# xbee_Featherwing.net
KiCad netlist of a schematic drawn in EAGLE
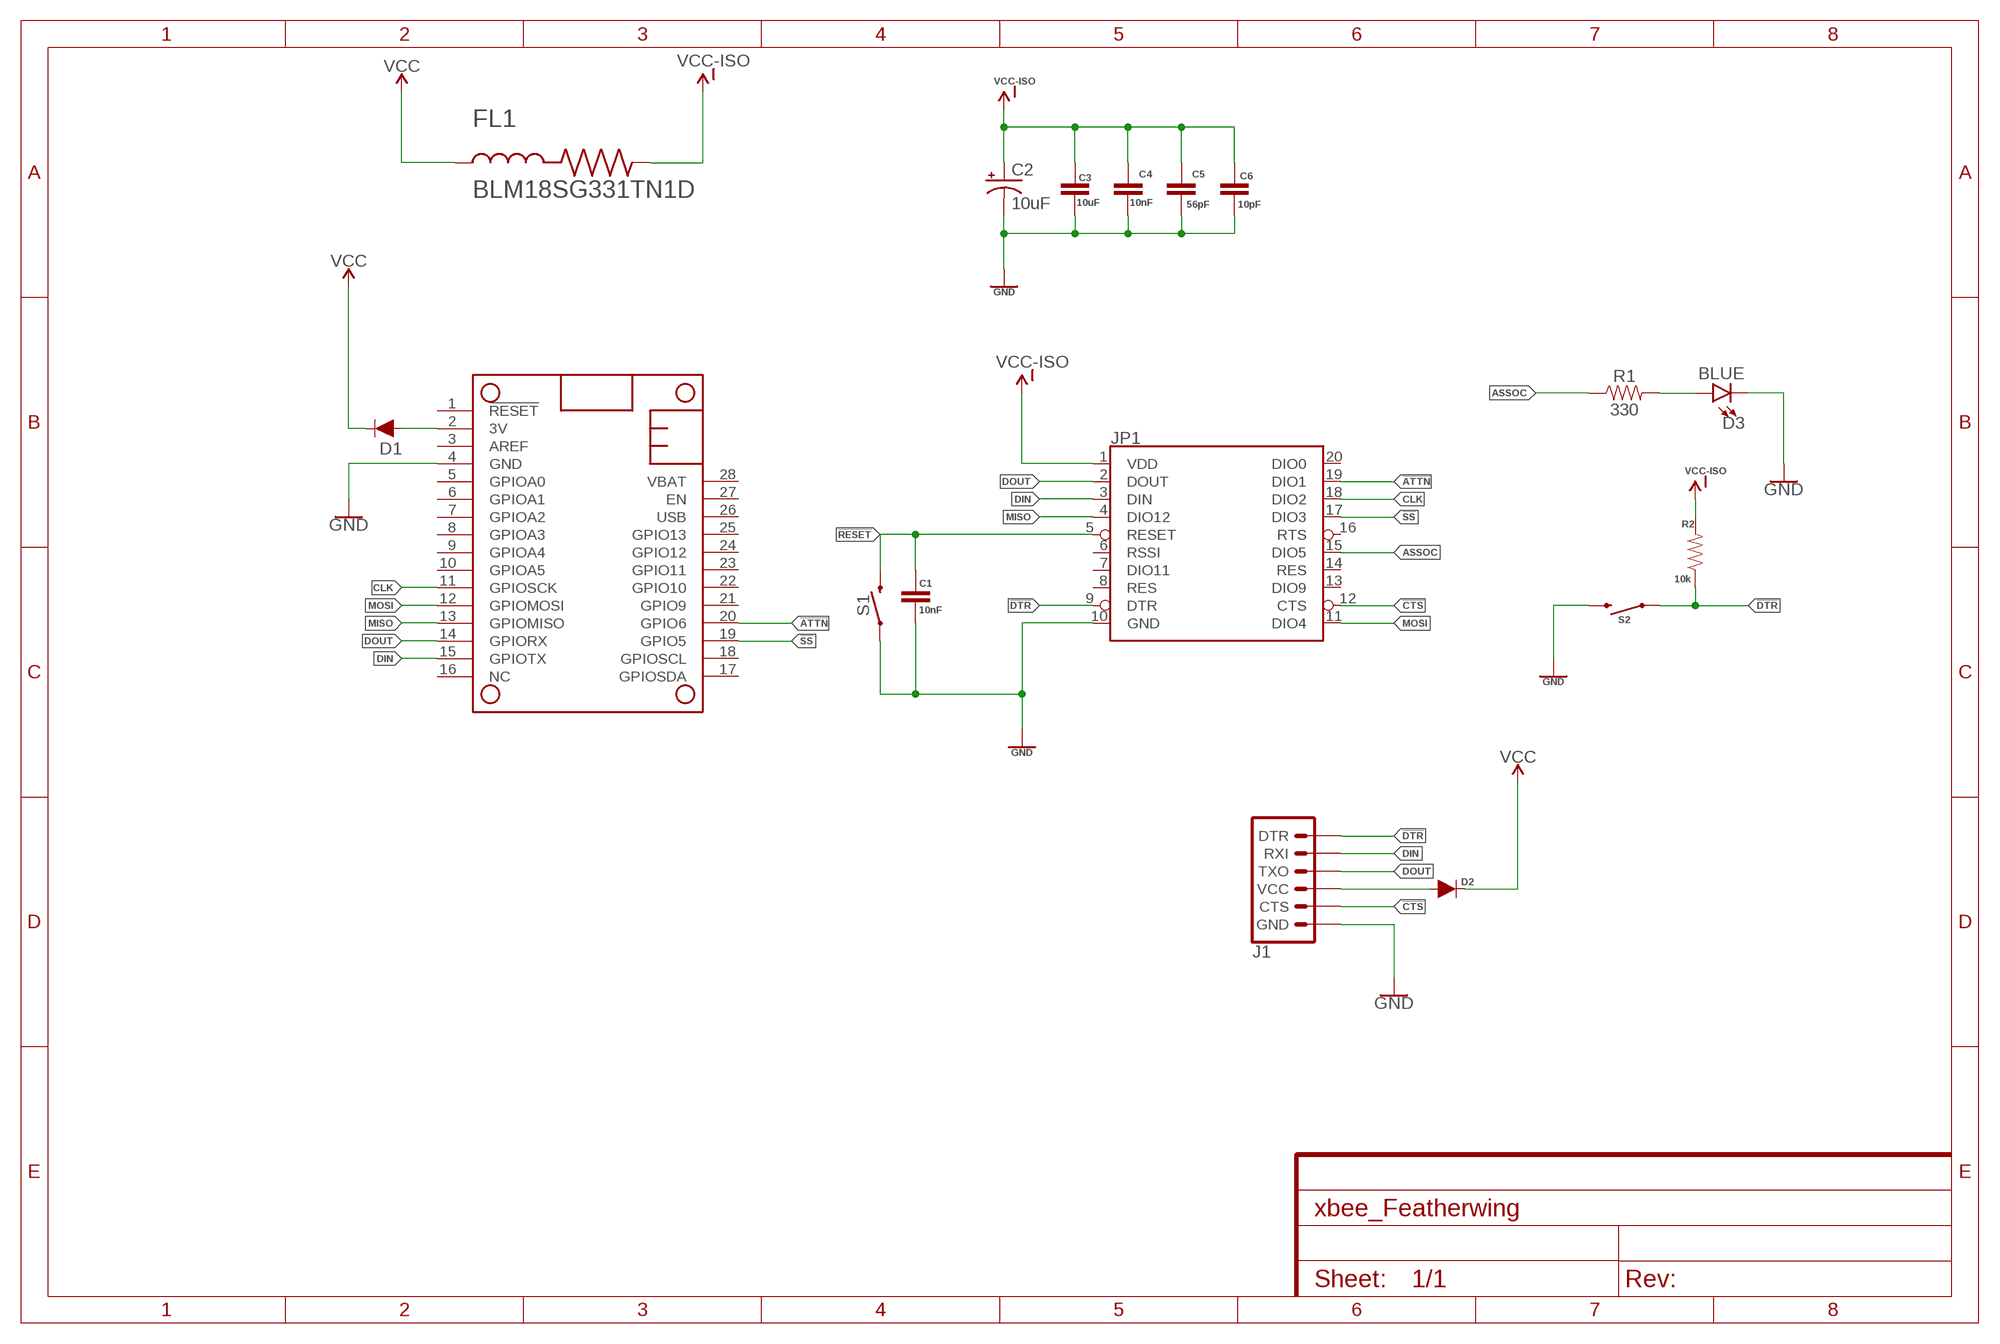
[diagram p0: schematic, sheet 1]

(export (version "E")
  (design (tool "Eeschema 10.0.6"))
  (components
    (comp (ref "C1")
      (value "10nF")
      (footprint "eagle-import:0603")
      (libsource (lib "eagle-import") (part "10NF-0603-50V-10%"))
    )
    (comp (ref "C2")
      (value "10uF")
      (footprint "eagle-import:EIA3216")
      (libsource (lib "eagle-import") (part "10UF-POLAR-EIA3216-16V-10%(TANT)"))
    )
    (comp (ref "C3")
      (value "10uF")
      (footprint "eagle-import:0603")
      (libsource (lib "eagle-import") (part "10UF-0603-6.3V-20%"))
    )
    (comp (ref "C4")
      (value "10nF")
      (footprint "eagle-import:0603")
      (libsource (lib "eagle-import") (part "10NF-0603-50V-10%"))
    )
    (comp (ref "C5")
      (value "56pF")
      (footprint "eagle-import:0603")
      (libsource (lib "eagle-import") (part "560PF-0603-50V-5%"))
    )
    (comp (ref "C6")
      (value "10pF")
      (footprint "eagle-import:0603")
      (libsource (lib "eagle-import") (part "10PF-0603-50V-5%"))
    )
    (comp (ref "D1")
      (value "250mA/100V")
      (footprint "eagle-import:SOD-323")
      (libsource (lib "eagle-import") (part "DIODE-BAS16J"))
    )
    (comp (ref "D2")
      (value "250mA/100V")
      (footprint "eagle-import:SOD-323")
      (libsource (lib "eagle-import") (part "DIODE-BAS16J"))
    )
    (comp (ref "D3")
      (value "BLUE")
      (footprint "eagle-import:LED-0603")
      (libsource (lib "eagle-import") (part "LED-BLUE0603"))
    )
    (comp (ref "FL1")
      (value "BLM18SG331TN1D")
      (footprint "eagle-import:BEADC1608X65N")
      (fields (field (name "MF") "Murata Electronics"))
      (libsource (lib "eagle-import") (part "BLM18SG331TN1D"))
    )
    (comp (ref "J1")
      (value "6_PIN_SERIAL_TARGETSILK")
      (footprint "eagle-import:6_PIN_SERIAL_TARGET_SIDE_W_SILK")
      (libsource (lib "eagle-import") (part "6_PIN_SERIAL_TARGETSILK"))
    )
    (comp (ref "JP1")
      (value "XBEESMD")
      (footprint "eagle-import:XBEE-SMD")
      (libsource (lib "eagle-import") (part "XBEESMD"))
    )
    (comp (ref "MS1")
      (value "FEATHERWINGXBEE")
      (footprint "eagle-import:FEATHERWING_XBEE")
      (libsource (lib "eagle-import") (part "FEATHERWINGXBEE"))
    )
    (comp (ref "R1")
      (value "330")
      (footprint "eagle-import:0603")
      (libsource (lib "eagle-import") (part "330OHM-0603-1/10W-1%"))
    )
    (comp (ref "R2")
      (value "10k")
      (footprint "eagle-import:0603")
      (libsource (lib "eagle-import") (part "10KOHM-0603-1/10W-1%"))
    )
    (comp (ref "S1")
      (value "MOMENTARY-SWITCH-SPST-PTH-6.0MM")
      (footprint "eagle-import:TACTILE_SWITCH_PTH_6.0MM")
      (libsource (lib "eagle-import") (part "MOMENTARY-SWITCH-SPST-PTH-6.0MM"))
    )
    (comp (ref "S2")
      (value "MOMENTARY-SWITCH-SPST-PTH-6.0MM")
      (footprint "eagle-import:TACTILE_SWITCH_PTH_6.0MM")
      (libsource (lib "eagle-import") (part "MOMENTARY-SWITCH-SPST-PTH-6.0MM"))
    )
  )
  (nets
    (net (code "1") (name "/USB") (class "Default")
      (node (ref "MS1") (pin "26") (pinfunction "USB_26") (pintype "power_in"))
    )
    (net (code "2") (name "/VBAT") (class "Default")
      (node (ref "MS1") (pin "28") (pinfunction "VBAT_28") (pintype "power_in"))
    )
    (net (code "3") (name "/~{ATTN}") (class "Default")
      (node (ref "JP1") (pin "19") (pinfunction "DIO1_19") (pintype "bidirectional"))
      (node (ref "MS1") (pin "20") (pinfunction "GPIO6_20") (pintype "bidirectional"))
    )
    (net (code "4") (name "/~{CTS}") (class "Default")
      (node (ref "J1") (pin "P$5") (pinfunction "CTS_P$5") (pintype "passive"))
      (node (ref "JP1") (pin "12") (pinfunction "CTS_12") (pintype "output"))
    )
    (net (code "5") (name "/~{DTR}") (class "Default")
      (node (ref "J1") (pin "P$1") (pinfunction "DTR_P$1") (pintype "passive"))
      (node (ref "JP1") (pin "9") (pinfunction "DTR_9") (pintype "bidirectional"))
      (node (ref "R2") (pin "1") (pinfunction "1_1") (pintype "passive"))
      (node (ref "S2") (pin "1") (pinfunction "1_1") (pintype "passive"))
    )
    (net (code "6") (name "/~{RESET}") (class "Default")
      (node (ref "C1") (pin "1") (pinfunction "1_1") (pintype "passive"))
      (node (ref "JP1") (pin "5") (pinfunction "RESET_5") (pintype "input"))
      (node (ref "S1") (pin "3") (pinfunction "2_3") (pintype "passive"))
    )
    (net (code "7") (name "/~{SS}") (class "Default")
      (node (ref "JP1") (pin "17") (pinfunction "DIO3_17") (pintype "bidirectional"))
      (node (ref "MS1") (pin "19") (pinfunction "GPIO5_19") (pintype "bidirectional"))
    )
    (net (code "8") (name "ASSOC") (class "Default")
      (node (ref "JP1") (pin "15") (pinfunction "DIO5_15") (pintype "bidirectional"))
      (node (ref "R1") (pin "1") (pinfunction "1_1") (pintype "passive"))
    )
    (net (code "9") (name "CLK") (class "Default")
      (node (ref "JP1") (pin "18") (pinfunction "DIO2_18") (pintype "bidirectional"))
      (node (ref "MS1") (pin "11") (pinfunction "GPIOSCK_11") (pintype "bidirectional"))
    )
    (net (code "10") (name "DIN") (class "Default")
      (node (ref "J1") (pin "P$3") (pinfunction "RXI_P$3") (pintype "passive"))
      (node (ref "JP1") (pin "3") (pinfunction "DIN_3") (pintype "input"))
      (node (ref "MS1") (pin "15") (pinfunction "GPIOTX_15") (pintype "bidirectional"))
    )
    (net (code "11") (name "DOUT") (class "Default")
      (node (ref "J1") (pin "P$2") (pinfunction "TXO_P$2") (pintype "passive"))
      (node (ref "JP1") (pin "2") (pinfunction "DOUT_2") (pintype "output"))
      (node (ref "MS1") (pin "14") (pinfunction "GPIORX_14") (pintype "bidirectional"))
    )
    (net (code "12") (name "GND") (class "Default")
      (node (ref "C1") (pin "2") (pinfunction "2_2") (pintype "passive"))
      (node (ref "C2") (pin "-") (pinfunction "-_-") (pintype "passive"))
      (node (ref "C3") (pin "2") (pinfunction "2_2") (pintype "passive"))
      (node (ref "C4") (pin "2") (pinfunction "2_2") (pintype "passive"))
      (node (ref "C5") (pin "2") (pinfunction "2_2") (pintype "passive"))
      (node (ref "C6") (pin "2") (pinfunction "2_2") (pintype "passive"))
      (node (ref "D3") (pin "C") (pinfunction "C_C") (pintype "passive"))
      (node (ref "J1") (pin "P$6") (pinfunction "GND_P$6") (pintype "passive"))
      (node (ref "JP1") (pin "10") (pinfunction "GND_10") (pintype "power_in"))
      (node (ref "MS1") (pin "4") (pinfunction "GND_4") (pintype "power_in"))
      (node (ref "S1") (pin "1") (pinfunction "1_1") (pintype "passive"))
      (node (ref "S2") (pin "3") (pinfunction "2_3") (pintype "passive"))
    )
    (net (code "13") (name "MISO") (class "Default")
      (node (ref "JP1") (pin "4") (pinfunction "DIO12_4") (pintype "bidirectional"))
      (node (ref "MS1") (pin "13") (pinfunction "GPIOMISO_13") (pintype "bidirectional"))
    )
    (net (code "14") (name "MOSI") (class "Default")
      (node (ref "JP1") (pin "11") (pinfunction "DIO4_11") (pintype "bidirectional"))
      (node (ref "MS1") (pin "12") (pinfunction "GPIOMOSI_12") (pintype "bidirectional"))
    )
    (net (code "15") (name "Net-(D3-PadA)") (class "Default")
      (node (ref "D3") (pin "A") (pinfunction "A_A") (pintype "passive"))
      (node (ref "R1") (pin "2") (pinfunction "2_2") (pintype "passive"))
    )
    (net (code "16") (name "Net-(J1-VCC)") (class "Default")
      (node (ref "D2") (pin "A") (pinfunction "A_A") (pintype "passive"))
      (node (ref "J1") (pin "P$4") (pinfunction "VCC_P$4") (pintype "passive"))
    )
    (net (code "17") (name "Net-(MS1-3V)") (class "Default")
      (node (ref "D1") (pin "A") (pinfunction "A_A") (pintype "passive"))
      (node (ref "MS1") (pin "2") (pinfunction "3V_2") (pintype "power_in"))
    )
    (net (code "18") (name "VCC") (class "Default")
      (node (ref "D1") (pin "C") (pinfunction "C_C") (pintype "passive"))
      (node (ref "D2") (pin "C") (pinfunction "C_C") (pintype "passive"))
      (node (ref "FL1") (pin "1") (pinfunction "1_1") (pintype "passive"))
    )
    (net (code "19") (name "VCC-ISO") (class "Default")
      (node (ref "C2") (pin "+") (pinfunction "+_+") (pintype "passive"))
      (node (ref "C3") (pin "1") (pinfunction "1_1") (pintype "passive"))
      (node (ref "C4") (pin "1") (pinfunction "1_1") (pintype "passive"))
      (node (ref "C5") (pin "1") (pinfunction "1_1") (pintype "passive"))
      (node (ref "C6") (pin "1") (pinfunction "1_1") (pintype "passive"))
      (node (ref "FL1") (pin "2") (pinfunction "2_2") (pintype "passive"))
      (node (ref "JP1") (pin "1") (pinfunction "VDD_1") (pintype "power_in"))
      (node (ref "R2") (pin "2") (pinfunction "2_2") (pintype "passive"))
    )
    (net (code "20") (name "unconnected-(JP1-DIO0-Pad20)") (class "Default")
      (node (ref "JP1") (pin "20") (pinfunction "DIO0_20") (pintype "bidirectional"))
    )
    (net (code "21") (name "unconnected-(JP1-DIO9-Pad13)") (class "Default")
      (node (ref "JP1") (pin "13") (pinfunction "DIO9_13") (pintype "bidirectional"))
    )
    (net (code "22") (name "unconnected-(JP1-DIO11-Pad7)") (class "Default")
      (node (ref "JP1") (pin "7") (pinfunction "DIO11_7") (pintype "bidirectional"))
    )
    (net (code "23") (name "unconnected-(JP1-RES-Pad8)") (class "Default")
      (node (ref "JP1") (pin "8") (pinfunction "RES_8") (pintype "bidirectional"))
    )
    (net (code "24") (name "unconnected-(JP1-RES-Pad14)") (class "Default")
      (node (ref "JP1") (pin "14") (pinfunction "RES_14") (pintype "bidirectional"))
    )
    (net (code "25") (name "unconnected-(JP1-RSSI-Pad6)") (class "Default")
      (node (ref "JP1") (pin "6") (pinfunction "RSSI_6") (pintype "bidirectional"))
    )
    (net (code "26") (name "unconnected-(JP1-RTS-Pad16)") (class "Default")
      (node (ref "JP1") (pin "16") (pinfunction "RTS_16") (pintype "input"))
    )
    (net (code "27") (name "unconnected-(MS1-AREF-Pad3)") (class "Default")
      (node (ref "MS1") (pin "3") (pinfunction "AREF_3") (pintype "passive"))
    )
    (net (code "28") (name "unconnected-(MS1-EN-Pad27)") (class "Default")
      (node (ref "MS1") (pin "27") (pinfunction "EN_27") (pintype "passive"))
    )
    (net (code "29") (name "unconnected-(MS1-GPIO9-Pad21)") (class "Default")
      (node (ref "MS1") (pin "21") (pinfunction "GPIO9_21") (pintype "bidirectional"))
    )
    (net (code "30") (name "unconnected-(MS1-GPIO10-Pad22)") (class "Default")
      (node (ref "MS1") (pin "22") (pinfunction "GPIO10_22") (pintype "bidirectional"))
    )
    (net (code "31") (name "unconnected-(MS1-GPIO11-Pad23)") (class "Default")
      (node (ref "MS1") (pin "23") (pinfunction "GPIO11_23") (pintype "bidirectional"))
    )
    (net (code "32") (name "unconnected-(MS1-GPIO12-Pad24)") (class "Default")
      (node (ref "MS1") (pin "24") (pinfunction "GPIO12_24") (pintype "bidirectional"))
    )
    (net (code "33") (name "unconnected-(MS1-GPIO13-Pad25)") (class "Default")
      (node (ref "MS1") (pin "25") (pinfunction "GPIO13_25") (pintype "bidirectional"))
    )
    (net (code "34") (name "unconnected-(MS1-GPIOA0-Pad5)") (class "Default")
      (node (ref "MS1") (pin "5") (pinfunction "GPIOA0_5") (pintype "bidirectional"))
    )
    (net (code "35") (name "unconnected-(MS1-GPIOA1-Pad6)") (class "Default")
      (node (ref "MS1") (pin "6") (pinfunction "GPIOA1_6") (pintype "bidirectional"))
    )
    (net (code "36") (name "unconnected-(MS1-GPIOA2-Pad7)") (class "Default")
      (node (ref "MS1") (pin "7") (pinfunction "GPIOA2_7") (pintype "bidirectional"))
    )
    (net (code "37") (name "unconnected-(MS1-GPIOA3-Pad8)") (class "Default")
      (node (ref "MS1") (pin "8") (pinfunction "GPIOA3_8") (pintype "bidirectional"))
    )
    (net (code "38") (name "unconnected-(MS1-GPIOA4-Pad9)") (class "Default")
      (node (ref "MS1") (pin "9") (pinfunction "GPIOA4_9") (pintype "bidirectional"))
    )
    (net (code "39") (name "unconnected-(MS1-GPIOA5-Pad10)") (class "Default")
      (node (ref "MS1") (pin "10") (pinfunction "GPIOA5_10") (pintype "bidirectional"))
    )
    (net (code "40") (name "unconnected-(MS1-GPIOSCL-Pad18)") (class "Default")
      (node (ref "MS1") (pin "18") (pinfunction "GPIOSCL_18") (pintype "bidirectional"))
    )
    (net (code "41") (name "unconnected-(MS1-GPIOSDA-Pad17)") (class "Default")
      (node (ref "MS1") (pin "17") (pinfunction "GPIOSDA_17") (pintype "bidirectional"))
    )
    (net (code "42") (name "unconnected-(MS1-NC-Pad16)") (class "Default")
      (node (ref "MS1") (pin "16") (pinfunction "NC_16") (pintype "passive"))
    )
    (net (code "43") (name "unconnected-(MS1-~{RESET}-Pad1)") (class "Default")
      (node (ref "MS1") (pin "1") (pinfunction "~{RESET}_1") (pintype "input"))
    )
  )
)
